# 2_MCU.net
KiCad netlist of a schematic drawn in Altium Designer
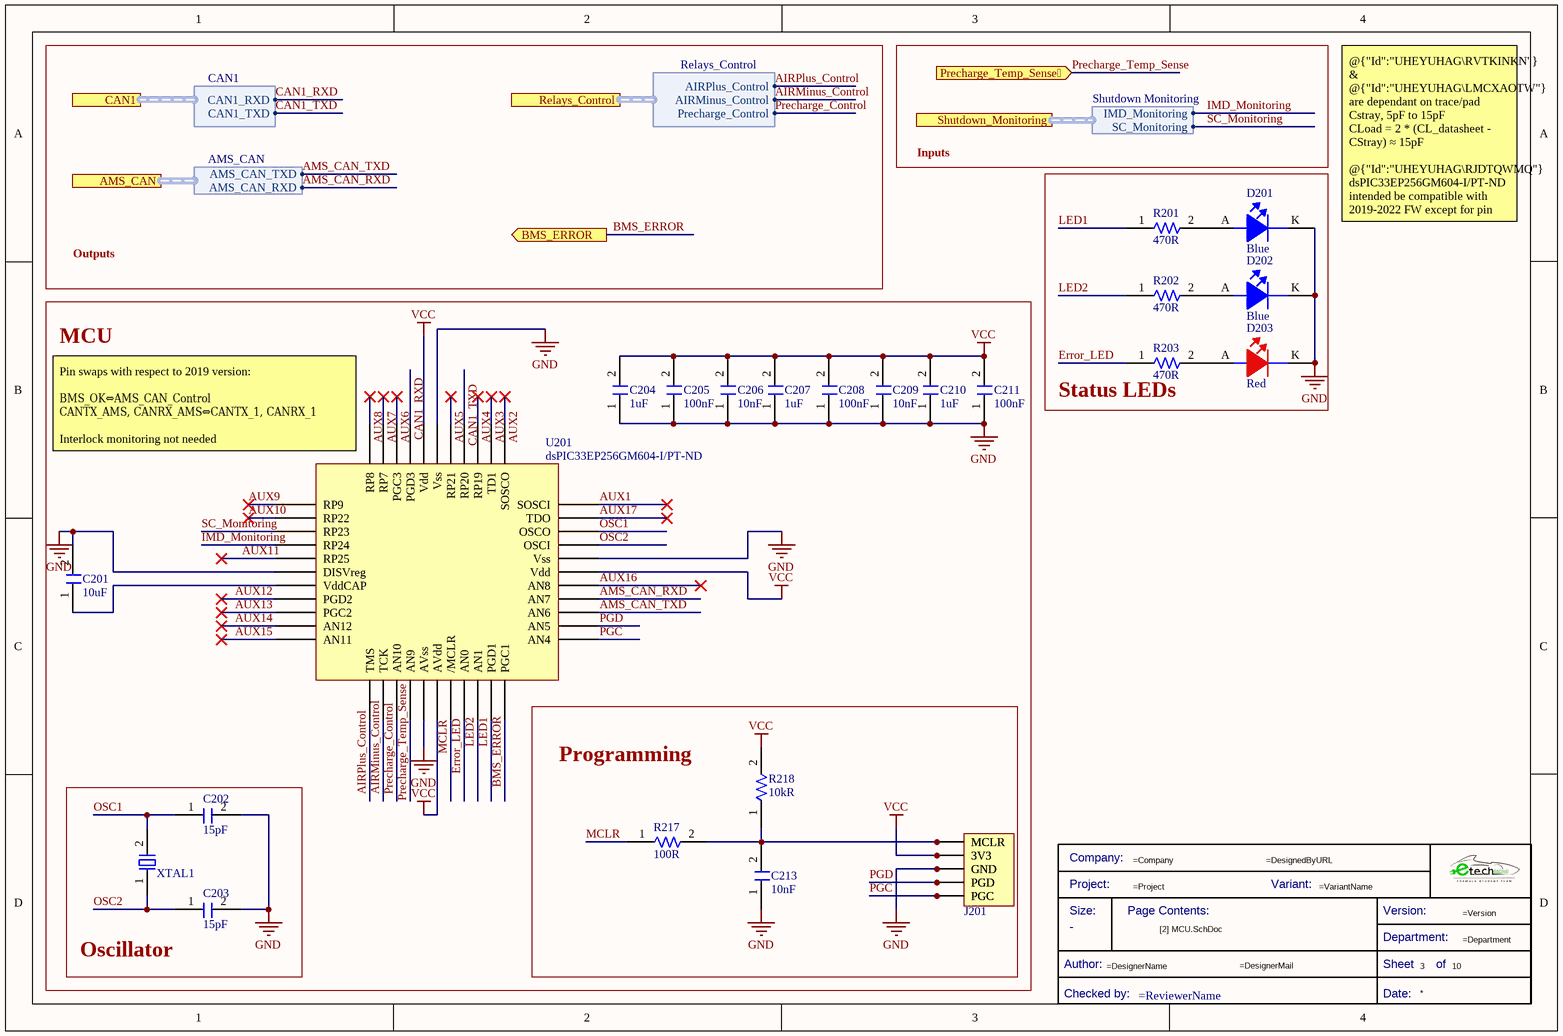
[diagram p0: [2] MCU.SchDoc]

(export (version "E")
  (design (tool "Eeschema 10.0.6"))
  (components
    (comp (ref "*")
      (value "Title Block_template")
      (description "Standard Title Block")
      (fields (field (name "SIZE") "-"))
      (libsource (lib "e-Tech_Racing") (part "Title Block_template"))
    )
    (comp (ref "C201")
      (value "885012208018")
      (footprint "C1206FNPC-RW")
      (description "Cap, 10ΜF, 10V, 10%, X7R, 1206")
      (fields
        (field (name "TOLERANCE") "10%")
        (field (name "CAPACITANCE") "10uF")
        (field (name ".CREATOR") "GP")
      )
      (libsource (lib "Passives") (part "C10u-10V-1206FNPC-X7R"))
    )
    (comp (ref "C202")
      (value "885012007052")
      (footprint "C0805FNPC-R")
      (description "Cap, 15PF, 50V, 5%, C0G/NP0, 0805")
      (fields
        (field (name "TOLERANCE") "5%")
        (field (name "CAPACITANCE") "15pF")
        (field (name ".CREATOR") "DR")
      )
      (libsource (lib "Passives") (part "C15p-50V-0805FNPC-NP0"))
    )
    (comp (ref "C203")
      (value "885012007052")
      (footprint "C0805FNPC-R")
      (description "Cap, 15PF, 50V, 5%, C0G/NP0, 0805")
      (fields
        (field (name "TOLERANCE") "5%")
        (field (name "CAPACITANCE") "15pF")
        (field (name ".CREATOR") "DR")
      )
      (libsource (lib "Passives") (part "C15p-50V-0805FNPC-NP0"))
    )
    (comp (ref "C204")
      (value "885012207103")
      (footprint "C0805FNPC-R")
      (fields
        (field (name "TOLERANCE") "10%")
        (field (name "CAPACITANCE") "1uF")
        (field (name ".CREATOR") "GP")
      )
      (libsource (lib "Passives") (part "C1u-50V-0805FNPC-X7R"))
    )
    (comp (ref "C205")
      (value "885012207098")
      (footprint "C0805FNPC-R")
      (description "Cap, 0.1ΜF, 50V, 10%, X7R, 0805")
      (fields
        (field (name "TOLERANCE") "10%")
        (field (name "CAPACITANCE") "100nF")
        (field (name ".CREATOR") "DR")
      )
      (libsource (lib "Passives") (part "C100n-50V-0805FNPC-X7R"))
    )
    (comp (ref "C206")
      (value "885012207092")
      (footprint "C0805FNPC-R")
      (description "Cap, 0.01ΜF, 50V, 10%, X7R, 0805")
      (fields
        (field (name "TOLERANCE") "10%")
        (field (name "CAPACITANCE") "10nF")
        (field (name ".CREATOR") "DR")
      )
      (libsource (lib "Passives") (part "C10n-50V-0805FNPC-X7R"))
    )
    (comp (ref "C207")
      (value "885012207103")
      (footprint "C0805FNPC-R")
      (fields
        (field (name "TOLERANCE") "10%")
        (field (name "CAPACITANCE") "1uF")
        (field (name ".CREATOR") "GP")
      )
      (libsource (lib "Passives") (part "C1u-50V-0805FNPC-X7R"))
    )
    (comp (ref "C208")
      (value "885012207098")
      (footprint "C0805FNPC-R")
      (description "Cap, 0.1ΜF, 50V, 10%, X7R, 0805")
      (fields
        (field (name "TOLERANCE") "10%")
        (field (name "CAPACITANCE") "100nF")
        (field (name ".CREATOR") "DR")
      )
      (libsource (lib "Passives") (part "C100n-50V-0805FNPC-X7R"))
    )
    (comp (ref "C209")
      (value "885012207092")
      (footprint "C0805FNPC-R")
      (description "Cap, 0.01ΜF, 50V, 10%, X7R, 0805")
      (fields
        (field (name "TOLERANCE") "10%")
        (field (name "CAPACITANCE") "10nF")
        (field (name ".CREATOR") "DR")
      )
      (libsource (lib "Passives") (part "C10n-50V-0805FNPC-X7R"))
    )
    (comp (ref "C210")
      (value "885012207103")
      (footprint "C0805FNPC-R")
      (fields
        (field (name "TOLERANCE") "10%")
        (field (name "CAPACITANCE") "1uF")
        (field (name ".CREATOR") "GP")
      )
      (libsource (lib "Passives") (part "C1u-50V-0805FNPC-X7R"))
    )
    (comp (ref "C211")
      (value "885012207098")
      (footprint "C0805FNPC-R")
      (description "Cap, 0.1ΜF, 50V, 10%, X7R, 0805")
      (fields
        (field (name "TOLERANCE") "10%")
        (field (name "CAPACITANCE") "100nF")
        (field (name ".CREATOR") "DR")
      )
      (libsource (lib "Passives") (part "C100n-50V-0805FNPC-X7R"))
    )
    (comp (ref "C213")
      (value "885012207092")
      (footprint "C0805FNPC-R")
      (description "Cap, 0.01ΜF, 50V, 10%, X7R, 0805")
      (fields
        (field (name "TOLERANCE") "10%")
        (field (name "CAPACITANCE") "10nF")
        (field (name ".CREATOR") "DR")
      )
      (libsource (lib "Passives") (part "C10n-50V-0805FNPC-X7R"))
    )
    (comp (ref "D201")
      (value "150080BS75000")
      (footprint "LED_0805_WE")
      (description "LED BLUE CLEAR 0805 SMD")
      (fields (field (name "COLOR") "Blue") (field (name ".CREATOR") "GP"))
      (libsource (lib "Semiconductor") (part "LEDBS-0805-145"))
    )
    (comp (ref "D202")
      (value "150080BS75000")
      (footprint "LED_0805_WE")
      (description "LED BLUE CLEAR 0805 SMD")
      (fields (field (name "COLOR") "Blue") (field (name ".CREATOR") "GP"))
      (libsource (lib "Semiconductor") (part "LEDBS-0805-145"))
    )
    (comp (ref "D203")
      (value "150080RS75000")
      (footprint "LED_0805_WE")
      (description "0805(H=0.8mm) 红色 高亮 λD=625nm VF=2V IF=30mA PD=72mW")
      (fields (field (name "COLOR") "Red") (field (name ".CREATOR") "DR"))
      (libsource (lib "Semiconductor") (part "LEDRS-0805-150"))
    )
    (comp (ref "J201")
      (value "61300511121")
      (footprint "J_PinHeader_1x5")
      (description "THT Vertical Pin Header WR-PHD, Pitch 2.54 mm, Single Row, 5 pins")
      (fields (field (name "MANUFACTURER") "Molex") (field (name ".CREATOR") "GP"))
      (libsource (lib "Electromechanical") (part "J_Pickit3"))
    )
    (comp (ref "R201")
      (value "CR0805-FX-4700GLF")
      (footprint "R0805FTK")
      (description "Res Thick Film 0805 470 Ohm 1% 1/8W ±100ppm/°C Molded SMD SMD Paper Tape on Plastic Reel")
      (fields
        (field (name "TOLERANCE") "1%")
        (field (name "RESISTANCE") "470R")
        (field (name ".CREATOR") "DR")
      )
      (libsource (lib "Passives") (part "R470-0805FTK"))
    )
    (comp (ref "R202")
      (value "CR0805-FX-4700GLF")
      (footprint "R0805FTK")
      (description "Res Thick Film 0805 470 Ohm 1% 1/8W ±100ppm/°C Molded SMD SMD Paper Tape on Plastic Reel")
      (fields
        (field (name "TOLERANCE") "1%")
        (field (name "RESISTANCE") "470R")
        (field (name ".CREATOR") "DR")
      )
      (libsource (lib "Passives") (part "R470-0805FTK"))
    )
    (comp (ref "R203")
      (value "CR0805-FX-4700GLF")
      (footprint "R0805FTK")
      (description "Res Thick Film 0805 470 Ohm 1% 1/8W ±100ppm/°C Molded SMD SMD Paper Tape on Plastic Reel")
      (fields
        (field (name "TOLERANCE") "1%")
        (field (name "RESISTANCE") "470R")
        (field (name ".CREATOR") "DR")
      )
      (libsource (lib "Passives") (part "R470-0805FTK"))
    )
    (comp (ref "R217")
      (value "CR0805-FX-1000ELF")
      (footprint "R0805FTK")
      (description "Res Thick Film 0805 100 Ohm 1% 1/8W ±100ppm/°C Molded SMD SMD Paper Tape on Plastic Reel")
      (fields
        (field (name "TOLERANCE") "1%")
        (field (name "RESISTANCE") "100R")
        (field (name ".CREATOR") "DR")
      )
      (libsource (lib "Passives") (part "R100-0805FTK"))
    )
    (comp (ref "R218")
      (value "CR0805-JW-103ELF")
      (footprint "R0805FTK")
      (fields
        (field (name "TOLERANCE") "5%")
        (field (name "RESISTANCE") "10kR")
        (field (name ".CREATOR") "DR")
      )
      (libsource (lib "Passives") (part "R10k-0805FTK"))
    )
    (comp (ref "U201")
      (value "dsPIC33EP256GM604-I/PT")
      (footprint "U_dsPIC33EP256GM604-I/PT")
      (description "16-bit MCU/DSC, 256 KB, 32768 Bytes, 70 MHz, 3 to 3.6V, TQFP-44, RoHS")
      (fields
        (field (name "SUPPLIER PART NUMBER 1") "dsPIC33EP256GM604-I/PT-ND")
        (field (name ".CREATOR") "DR")
      )
      (libsource (lib "Integrated circuits") (part "U_dsPIC33EP256GM604-I/PT"))
    )
    (comp (ref "XTAL1")
      (value "830028710")
      (footprint "XTAL20M_SMD")
      (description "830028710, 20 MHz")
      (fields (field (name "MANUFACTURER") "Würth Elektronik") (field (name ".CREATOR") "GP"))
      (libsource (lib "Passives") (part "XTAL20M_SMD"))
    )
  )
  (nets
    (net (code "6") (name "/AIRMinus_Control") (class "Default")
      (node (ref "U201") (pin "13") (pinfunction "TCK_13") (pintype "passive"))
    )
    (net (code "7") (name "/AIRPlus_Control") (class "Default")
      (node (ref "U201") (pin "12") (pinfunction "TMS_12") (pintype "passive"))
    )
    (net (code "8") (name "/AMS_CAN_RXD") (class "Default")
      (node (ref "U201") (pin "26") (pinfunction "AN7_26") (pintype "passive"))
    )
    (net (code "9") (name "/AMS_CAN_TXD") (class "Default")
      (node (ref "U201") (pin "25") (pinfunction "AN6_25") (pintype "passive"))
    )
    (net (code "10") (name "/AUX1") (class "Default")
      (node (ref "U201") (pin "33") (pinfunction "SOSCI_33") (pintype "passive+no_connect"))
    )
    (net (code "11") (name "/AUX2") (class "Default")
      (node (ref "U201") (pin "34") (pinfunction "SOSCO_34") (pintype "passive+no_connect"))
    )
    (net (code "12") (name "/AUX3") (class "Default")
      (node (ref "U201") (pin "35") (pinfunction "TD1_35") (pintype "passive+no_connect"))
    )
    (net (code "13") (name "/AUX4") (class "Default")
      (node (ref "U201") (pin "36") (pinfunction "RP19_36") (pintype "passive+no_connect"))
    )
    (net (code "14") (name "/AUX5") (class "Default")
      (node (ref "U201") (pin "38") (pinfunction "RP21_38") (pintype "passive+no_connect"))
    )
    (net (code "15") (name "/AUX6") (class "Default")
      (node (ref "U201") (pin "42") (pinfunction "PGC3_42") (pintype "passive+no_connect"))
    )
    (net (code "16") (name "/AUX7") (class "Default")
      (node (ref "U201") (pin "43") (pinfunction "RP7_43") (pintype "passive+no_connect"))
    )
    (net (code "17") (name "/AUX8") (class "Default")
      (node (ref "U201") (pin "44") (pinfunction "RP8_44") (pintype "passive+no_connect"))
    )
    (net (code "18") (name "/AUX9") (class "Default")
      (node (ref "U201") (pin "1") (pinfunction "RP9_1") (pintype "passive+no_connect"))
    )
    (net (code "19") (name "/AUX10") (class "Default")
      (node (ref "U201") (pin "2") (pinfunction "RP22_2") (pintype "passive+no_connect"))
    )
    (net (code "20") (name "/AUX11") (class "Default")
      (node (ref "U201") (pin "5") (pinfunction "RP25_5") (pintype "passive+no_connect"))
    )
    (net (code "21") (name "/AUX12") (class "Default")
      (node (ref "U201") (pin "8") (pinfunction "PGD2_8") (pintype "passive+no_connect"))
    )
    (net (code "22") (name "/AUX13") (class "Default")
      (node (ref "U201") (pin "9") (pinfunction "PGC2_9") (pintype "passive+no_connect"))
    )
    (net (code "23") (name "/AUX14") (class "Default")
      (node (ref "U201") (pin "10") (pinfunction "AN12_10") (pintype "passive+no_connect"))
    )
    (net (code "24") (name "/AUX15") (class "Default")
      (node (ref "U201") (pin "11") (pinfunction "AN11_11") (pintype "passive+no_connect"))
    )
    (net (code "25") (name "/AUX16") (class "Default")
      (node (ref "U201") (pin "27") (pinfunction "AN8_27") (pintype "passive+no_connect"))
    )
    (net (code "26") (name "/AUX17") (class "Default")
      (node (ref "U201") (pin "32") (pinfunction "TDO_32") (pintype "passive+no_connect"))
    )
    (net (code "27") (name "/BMS_ERROR") (class "Default")
      (node (ref "U201") (pin "22") (pinfunction "PGC1_22") (pintype "passive"))
    )
    (net (code "28") (name "/CAN1_RXD") (class "Default")
      (node (ref "U201") (pin "41") (pinfunction "PGD3_41") (pintype "passive"))
    )
    (net (code "29") (name "/CAN1_TXD") (class "Default")
      (node (ref "U201") (pin "37") (pinfunction "RP20_37") (pintype "passive"))
    )
    (net (code "30") (name "/Error_LED") (class "Default")
      (node (ref "R203") (pin "1") (pinfunction "1_1") (pintype "passive"))
      (node (ref "U201") (pin "19") (pinfunction "AN0_19") (pintype "passive"))
    )
    (net (code "31") (name "/IMD_Monitoring") (class "Default")
      (node (ref "U201") (pin "4") (pinfunction "RP24_4") (pintype "passive"))
    )
    (net (code "32") (name "/LED1") (class "Default")
      (node (ref "R201") (pin "1") (pinfunction "1_1") (pintype "passive"))
      (node (ref "U201") (pin "21") (pinfunction "PGD1_21") (pintype "passive"))
    )
    (net (code "33") (name "/LED2") (class "Default")
      (node (ref "R202") (pin "1") (pinfunction "1_1") (pintype "passive"))
      (node (ref "U201") (pin "20") (pinfunction "AN1_20") (pintype "passive"))
    )
    (net (code "34") (name "/MCLR") (class "Default")
      (node (ref "R217") (pin "1") (pinfunction "1_1") (pintype "passive"))
      (node (ref "U201") (pin "18") (pinfunction "/MCLR_18") (pintype "passive"))
    )
    (net (code "35") (name "/OSC1") (class "Default")
      (node (ref "C202") (pin "1") (pinfunction "1_1") (pintype "passive"))
      (node (ref "U201") (pin "31") (pinfunction "OSCO_31") (pintype "passive"))
      (node (ref "XTAL1") (pin "2") (pinfunction "2_2") (pintype "passive"))
    )
    (net (code "36") (name "/OSC2") (class "Default")
      (node (ref "C203") (pin "1") (pinfunction "1_1") (pintype "passive"))
      (node (ref "U201") (pin "30") (pinfunction "OSCI_30") (pintype "passive"))
      (node (ref "XTAL1") (pin "1") (pinfunction "1_1") (pintype "passive"))
    )
    (net (code "37") (name "/PGC") (class "Default")
      (node (ref "J201") (pin "5") (pinfunction "PGC_5") (pintype "passive"))
      (node (ref "U201") (pin "23") (pinfunction "AN4_23") (pintype "passive"))
    )
    (net (code "38") (name "/PGD") (class "Default")
      (node (ref "J201") (pin "4") (pinfunction "PGD_4") (pintype "passive"))
      (node (ref "U201") (pin "24") (pinfunction "AN5_24") (pintype "passive"))
    )
    (net (code "39") (name "/Precharge_Control") (class "Default")
      (node (ref "U201") (pin "14") (pinfunction "AN10_14") (pintype "passive"))
    )
    (net (code "40") (name "/Precharge_Temp_Sense") (class "Default")
      (node (ref "U201") (pin "15") (pinfunction "AN9_15") (pintype "passive"))
    )
    (net (code "41") (name "/SC_Monitoring") (class "Default")
      (node (ref "U201") (pin "3") (pinfunction "RP23_3") (pintype "passive"))
    )
    (net (code "46") (name "GND") (class "Default")
      (node (ref "C201") (pin "2") (pinfunction "2_2") (pintype "passive"))
      (node (ref "C202") (pin "2") (pinfunction "2_2") (pintype "passive"))
      (node (ref "C203") (pin "2") (pinfunction "2_2") (pintype "passive"))
      (node (ref "C204") (pin "1") (pinfunction "1_1") (pintype "passive"))
      (node (ref "C205") (pin "1") (pinfunction "1_1") (pintype "passive"))
      (node (ref "C206") (pin "1") (pinfunction "1_1") (pintype "passive"))
      (node (ref "C207") (pin "1") (pinfunction "1_1") (pintype "passive"))
      (node (ref "C208") (pin "1") (pinfunction "1_1") (pintype "passive"))
      (node (ref "C209") (pin "1") (pinfunction "1_1") (pintype "passive"))
      (node (ref "C210") (pin "1") (pinfunction "1_1") (pintype "passive"))
      (node (ref "C211") (pin "1") (pinfunction "1_1") (pintype "passive"))
      (node (ref "C213") (pin "1") (pinfunction "1_1") (pintype "passive"))
      (node (ref "D201") (pin "K") (pinfunction "K_K") (pintype "passive"))
      (node (ref "D202") (pin "K") (pinfunction "K_K") (pintype "passive"))
      (node (ref "D203") (pin "K") (pinfunction "K_K") (pintype "passive"))
      (node (ref "J201") (pin "3") (pinfunction "GND_3") (pintype "passive"))
      (node (ref "U201") (pin "16") (pinfunction "AVss_16") (pintype "passive"))
      (node (ref "U201") (pin "29") (pinfunction "Vss_29") (pintype "passive"))
      (node (ref "U201") (pin "39") (pinfunction "Vss_39") (pintype "passive"))
      (node (ref "U201") (pin "6") (pinfunction "DISVreg_6") (pintype "passive"))
    )
    (net (code "47") (name "Net-(D201-PadA)") (class "Default")
      (node (ref "D201") (pin "A") (pinfunction "A_A") (pintype "passive"))
      (node (ref "R201") (pin "2") (pinfunction "2_2") (pintype "passive"))
    )
    (net (code "48") (name "Net-(D202-PadA)") (class "Default")
      (node (ref "D202") (pin "A") (pinfunction "A_A") (pintype "passive"))
      (node (ref "R202") (pin "2") (pinfunction "2_2") (pintype "passive"))
    )
    (net (code "49") (name "Net-(D203-PadA)") (class "Default")
      (node (ref "D203") (pin "A") (pinfunction "A_A") (pintype "passive"))
      (node (ref "R203") (pin "2") (pinfunction "2_2") (pintype "passive"))
    )
    (net (code "50") (name "Net-(J201-MCLR)") (class "Default")
      (node (ref "C213") (pin "2") (pinfunction "2_2") (pintype "passive"))
      (node (ref "J201") (pin "1") (pinfunction "MCLR_1") (pintype "passive"))
      (node (ref "R217") (pin "2") (pinfunction "2_2") (pintype "passive"))
      (node (ref "R218") (pin "1") (pinfunction "1_1") (pintype "passive"))
    )
    (net (code "51") (name "Net-(U201-VddCAP)") (class "Default")
      (node (ref "C201") (pin "1") (pinfunction "1_1") (pintype "passive"))
      (node (ref "U201") (pin "7") (pinfunction "VddCAP_7") (pintype "passive"))
    )
    (net (code "52") (name "VCC") (class "Default")
      (node (ref "C204") (pin "2") (pinfunction "2_2") (pintype "passive"))
      (node (ref "C205") (pin "2") (pinfunction "2_2") (pintype "passive"))
      (node (ref "C206") (pin "2") (pinfunction "2_2") (pintype "passive"))
      (node (ref "C207") (pin "2") (pinfunction "2_2") (pintype "passive"))
      (node (ref "C208") (pin "2") (pinfunction "2_2") (pintype "passive"))
      (node (ref "C209") (pin "2") (pinfunction "2_2") (pintype "passive"))
      (node (ref "C210") (pin "2") (pinfunction "2_2") (pintype "passive"))
      (node (ref "C211") (pin "2") (pinfunction "2_2") (pintype "passive"))
      (node (ref "J201") (pin "2") (pinfunction "3V3_2") (pintype "passive"))
      (node (ref "R218") (pin "2") (pinfunction "2_2") (pintype "passive"))
      (node (ref "U201") (pin "17") (pinfunction "AVdd_17") (pintype "passive"))
      (node (ref "U201") (pin "28") (pinfunction "Vdd_28") (pintype "passive"))
      (node (ref "U201") (pin "40") (pinfunction "Vdd_40") (pintype "passive"))
    )
  )
)
